# FPGA_Ground.net
KiCad netlist of a schematic drawn in Altium Designer
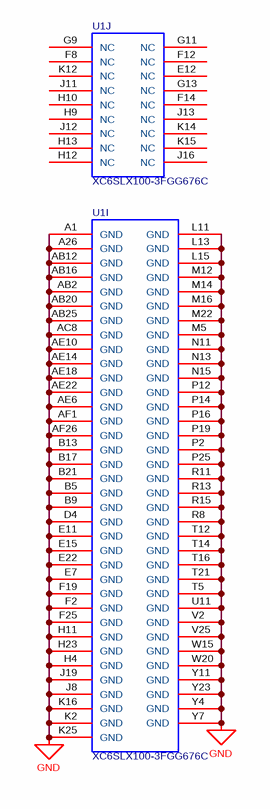
[diagram p0: FPGA_Ground.SchDoc]

(export (version "E")
  (design (tool "Eeschema 10.0.6"))
  (components
    (comp (ref "U1")
      (value "XC6SLX100-3FGG676C")
      (footprint "FGG676")
      (fields (field (name "MANUFACTURER") "Xilinx Inc."))
      (libsource (lib "ALCT_MEZ_SPARTAN6_Library") (part "XC6SLX100-3FGG676C"))
    )
  )
  (nets
    (net (code "1") (name "GND") (class "Default")
      (node (ref "U1") (pin "A1") (pinfunction "GND_A1") (pintype "power_in"))
      (node (ref "U1") (pin "A26") (pinfunction "GND_A26") (pintype "power_in"))
      (node (ref "U1") (pin "AB12") (pinfunction "GND_AB12") (pintype "power_in"))
      (node (ref "U1") (pin "AB16") (pinfunction "GND_AB16") (pintype "power_in"))
      (node (ref "U1") (pin "AB2") (pinfunction "GND_AB2") (pintype "power_in"))
      (node (ref "U1") (pin "AB20") (pinfunction "GND_AB20") (pintype "power_in"))
      (node (ref "U1") (pin "AB25") (pinfunction "GND_AB25") (pintype "power_in"))
      (node (ref "U1") (pin "AC8") (pinfunction "GND_AC8") (pintype "power_in"))
      (node (ref "U1") (pin "AE10") (pinfunction "GND_AE10") (pintype "power_in"))
      (node (ref "U1") (pin "AE14") (pinfunction "GND_AE14") (pintype "power_in"))
      (node (ref "U1") (pin "AE18") (pinfunction "GND_AE18") (pintype "power_in"))
      (node (ref "U1") (pin "AE22") (pinfunction "GND_AE22") (pintype "power_in"))
      (node (ref "U1") (pin "AE6") (pinfunction "GND_AE6") (pintype "power_in"))
      (node (ref "U1") (pin "AF1") (pinfunction "GND_AF1") (pintype "power_in"))
      (node (ref "U1") (pin "AF26") (pinfunction "GND_AF26") (pintype "power_in"))
      (node (ref "U1") (pin "B13") (pinfunction "GND_B13") (pintype "power_in"))
      (node (ref "U1") (pin "B17") (pinfunction "GND_B17") (pintype "power_in"))
      (node (ref "U1") (pin "B21") (pinfunction "GND_B21") (pintype "power_in"))
      (node (ref "U1") (pin "B5") (pinfunction "GND_B5") (pintype "power_in"))
      (node (ref "U1") (pin "B9") (pinfunction "GND_B9") (pintype "power_in"))
      (node (ref "U1") (pin "D4") (pinfunction "GND_D4") (pintype "power_in"))
      (node (ref "U1") (pin "E11") (pinfunction "GND_E11") (pintype "power_in"))
      (node (ref "U1") (pin "E15") (pinfunction "GND_E15") (pintype "power_in"))
      (node (ref "U1") (pin "E22") (pinfunction "GND_E22") (pintype "power_in"))
      (node (ref "U1") (pin "E7") (pinfunction "GND_E7") (pintype "power_in"))
      (node (ref "U1") (pin "F19") (pinfunction "GND_F19") (pintype "power_in"))
      (node (ref "U1") (pin "F2") (pinfunction "GND_F2") (pintype "power_in"))
      (node (ref "U1") (pin "F25") (pinfunction "GND_F25") (pintype "power_in"))
      (node (ref "U1") (pin "H11") (pinfunction "GND_H11") (pintype "power_in"))
      (node (ref "U1") (pin "H23") (pinfunction "GND_H23") (pintype "power_in"))
      (node (ref "U1") (pin "H4") (pinfunction "GND_H4") (pintype "power_in"))
      (node (ref "U1") (pin "J19") (pinfunction "GND_J19") (pintype "power_in"))
      (node (ref "U1") (pin "J8") (pinfunction "GND_J8") (pintype "power_in"))
      (node (ref "U1") (pin "K16") (pinfunction "GND_K16") (pintype "power_in"))
      (node (ref "U1") (pin "K2") (pinfunction "GND_K2") (pintype "power_in"))
      (node (ref "U1") (pin "K25") (pinfunction "GND_K25") (pintype "power_in"))
      (node (ref "U1") (pin "L11") (pinfunction "GND_L11") (pintype "power_in"))
      (node (ref "U1") (pin "L13") (pinfunction "GND_L13") (pintype "power_in"))
      (node (ref "U1") (pin "L15") (pinfunction "GND_L15") (pintype "power_in"))
      (node (ref "U1") (pin "M12") (pinfunction "GND_M12") (pintype "power_in"))
      (node (ref "U1") (pin "M14") (pinfunction "GND_M14") (pintype "power_in"))
      (node (ref "U1") (pin "M16") (pinfunction "GND_M16") (pintype "power_in"))
      (node (ref "U1") (pin "M22") (pinfunction "GND_M22") (pintype "power_in"))
      (node (ref "U1") (pin "M5") (pinfunction "GND_M5") (pintype "power_in"))
      (node (ref "U1") (pin "N11") (pinfunction "GND_N11") (pintype "power_in"))
      (node (ref "U1") (pin "N13") (pinfunction "GND_N13") (pintype "power_in"))
      (node (ref "U1") (pin "N15") (pinfunction "GND_N15") (pintype "power_in"))
      (node (ref "U1") (pin "P12") (pinfunction "GND_P12") (pintype "power_in"))
      (node (ref "U1") (pin "P14") (pinfunction "GND_P14") (pintype "power_in"))
      (node (ref "U1") (pin "P16") (pinfunction "GND_P16") (pintype "power_in"))
      (node (ref "U1") (pin "P19") (pinfunction "GND_P19") (pintype "power_in"))
      (node (ref "U1") (pin "P2") (pinfunction "GND_P2") (pintype "power_in"))
      (node (ref "U1") (pin "P25") (pinfunction "GND_P25") (pintype "power_in"))
      (node (ref "U1") (pin "R11") (pinfunction "GND_R11") (pintype "power_in"))
      (node (ref "U1") (pin "R13") (pinfunction "GND_R13") (pintype "power_in"))
      (node (ref "U1") (pin "R15") (pinfunction "GND_R15") (pintype "power_in"))
      (node (ref "U1") (pin "R8") (pinfunction "GND_R8") (pintype "power_in"))
      (node (ref "U1") (pin "T12") (pinfunction "GND_T12") (pintype "power_in"))
      (node (ref "U1") (pin "T14") (pinfunction "GND_T14") (pintype "power_in"))
      (node (ref "U1") (pin "T16") (pinfunction "GND_T16") (pintype "power_in"))
      (node (ref "U1") (pin "T21") (pinfunction "GND_T21") (pintype "power_in"))
      (node (ref "U1") (pin "T5") (pinfunction "GND_T5") (pintype "power_in"))
      (node (ref "U1") (pin "U11") (pinfunction "GND_U11") (pintype "power_in"))
      (node (ref "U1") (pin "V2") (pinfunction "GND_V2") (pintype "power_in"))
      (node (ref "U1") (pin "V25") (pinfunction "GND_V25") (pintype "power_in"))
      (node (ref "U1") (pin "W15") (pinfunction "GND_W15") (pintype "power_in"))
      (node (ref "U1") (pin "W20") (pinfunction "GND_W20") (pintype "power_in"))
      (node (ref "U1") (pin "Y11") (pinfunction "GND_Y11") (pintype "power_in"))
      (node (ref "U1") (pin "Y23") (pinfunction "GND_Y23") (pintype "power_in"))
      (node (ref "U1") (pin "Y4") (pinfunction "GND_Y4") (pintype "power_in"))
      (node (ref "U1") (pin "Y7") (pinfunction "GND_Y7") (pintype "power_in"))
    )
    (net (code "2") (name "unconnected-(U1J-NC-PadE12)") (class "Default")
      (node (ref "U1") (pin "E12") (pinfunction "NC_E12") (pintype "passive"))
    )
    (net (code "3") (name "unconnected-(U1J-NC-PadF8)") (class "Default")
      (node (ref "U1") (pin "F8") (pinfunction "NC_F8") (pintype "passive"))
    )
    (net (code "4") (name "unconnected-(U1J-NC-PadF12)") (class "Default")
      (node (ref "U1") (pin "F12") (pinfunction "NC_F12") (pintype "passive"))
    )
    (net (code "5") (name "unconnected-(U1J-NC-PadF14)") (class "Default")
      (node (ref "U1") (pin "F14") (pinfunction "NC_F14") (pintype "passive"))
    )
    (net (code "6") (name "unconnected-(U1J-NC-PadG9)") (class "Default")
      (node (ref "U1") (pin "G9") (pinfunction "NC_G9") (pintype "passive"))
    )
    (net (code "7") (name "unconnected-(U1J-NC-PadG11)") (class "Default")
      (node (ref "U1") (pin "G11") (pinfunction "NC_G11") (pintype "passive"))
    )
    (net (code "8") (name "unconnected-(U1J-NC-PadG13)") (class "Default")
      (node (ref "U1") (pin "G13") (pinfunction "NC_G13") (pintype "passive"))
    )
    (net (code "9") (name "unconnected-(U1J-NC-PadH9)") (class "Default")
      (node (ref "U1") (pin "H9") (pinfunction "NC_H9") (pintype "passive"))
    )
    (net (code "10") (name "unconnected-(U1J-NC-PadH10)") (class "Default")
      (node (ref "U1") (pin "H10") (pinfunction "NC_H10") (pintype "passive"))
    )
    (net (code "11") (name "unconnected-(U1J-NC-PadH12)") (class "Default")
      (node (ref "U1") (pin "H12") (pinfunction "NC_H12") (pintype "passive"))
    )
    (net (code "12") (name "unconnected-(U1J-NC-PadH13)") (class "Default")
      (node (ref "U1") (pin "H13") (pinfunction "NC_H13") (pintype "passive"))
    )
    (net (code "13") (name "unconnected-(U1J-NC-PadJ11)") (class "Default")
      (node (ref "U1") (pin "J11") (pinfunction "NC_J11") (pintype "passive"))
    )
    (net (code "14") (name "unconnected-(U1J-NC-PadJ12)") (class "Default")
      (node (ref "U1") (pin "J12") (pinfunction "NC_J12") (pintype "passive"))
    )
    (net (code "15") (name "unconnected-(U1J-NC-PadJ13)") (class "Default")
      (node (ref "U1") (pin "J13") (pinfunction "NC_J13") (pintype "passive"))
    )
    (net (code "16") (name "unconnected-(U1J-NC-PadJ16)") (class "Default")
      (node (ref "U1") (pin "J16") (pinfunction "NC_J16") (pintype "passive"))
    )
    (net (code "17") (name "unconnected-(U1J-NC-PadK12)") (class "Default")
      (node (ref "U1") (pin "K12") (pinfunction "NC_K12") (pintype "passive"))
    )
    (net (code "18") (name "unconnected-(U1J-NC-PadK14)") (class "Default")
      (node (ref "U1") (pin "K14") (pinfunction "NC_K14") (pintype "passive"))
    )
    (net (code "19") (name "unconnected-(U1J-NC-PadK15)") (class "Default")
      (node (ref "U1") (pin "K15") (pinfunction "NC_K15") (pintype "passive"))
    )
  )
)
